# human.net
KiCad netlist of a schematic drawn in EAGLE
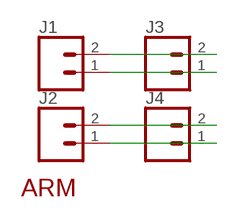
[diagram p0: schematic, sheet 1]

(export (version "E")
  (design (tool "Eeschema 10.0.6"))
  (components
    (comp (ref "J1")
      (value "CONN_02LOCK")
      (footprint "eagle-import:1X02_LOCK")
      (libsource (lib "eagle-import") (part "CONN_02LOCK"))
    )
    (comp (ref "J2")
      (value "CONN_02LOCK")
      (footprint "eagle-import:1X02_LOCK")
      (libsource (lib "eagle-import") (part "CONN_02LOCK"))
    )
    (comp (ref "J3")
      (value "CONN_02LOCK")
      (footprint "eagle-import:1X02_LOCK")
      (libsource (lib "eagle-import") (part "CONN_02LOCK"))
    )
    (comp (ref "J4")
      (value "CONN_02LOCK")
      (footprint "eagle-import:1X02_LOCK")
      (libsource (lib "eagle-import") (part "CONN_02LOCK"))
    )
    (comp (ref "U$1")
      (value "ARMHUMAN")
      (footprint "eagle-import:HUMAN")
      (libsource (lib "eagle-import") (part "ARMHUMAN"))
    )
  )
  (nets
    (net (code "1") (name "Net-(J1-Pad1)") (class "Default")
      (node (ref "J1") (pin "1") (pinfunction "1_1") (pintype "passive"))
      (node (ref "J3") (pin "1") (pinfunction "1_1") (pintype "passive"))
    )
    (net (code "2") (name "Net-(J1-Pad2)") (class "Default")
      (node (ref "J1") (pin "2") (pinfunction "2_2") (pintype "passive"))
      (node (ref "J3") (pin "2") (pinfunction "2_2") (pintype "passive"))
    )
    (net (code "3") (name "Net-(J2-Pad1)") (class "Default")
      (node (ref "J2") (pin "1") (pinfunction "1_1") (pintype "passive"))
      (node (ref "J4") (pin "1") (pinfunction "1_1") (pintype "passive"))
    )
    (net (code "4") (name "Net-(J2-Pad2)") (class "Default")
      (node (ref "J2") (pin "2") (pinfunction "2_2") (pintype "passive"))
      (node (ref "J4") (pin "2") (pinfunction "2_2") (pintype "passive"))
    )
  )
)
